# Connectors.net
KiCad netlist of a schematic drawn in Altium Designer
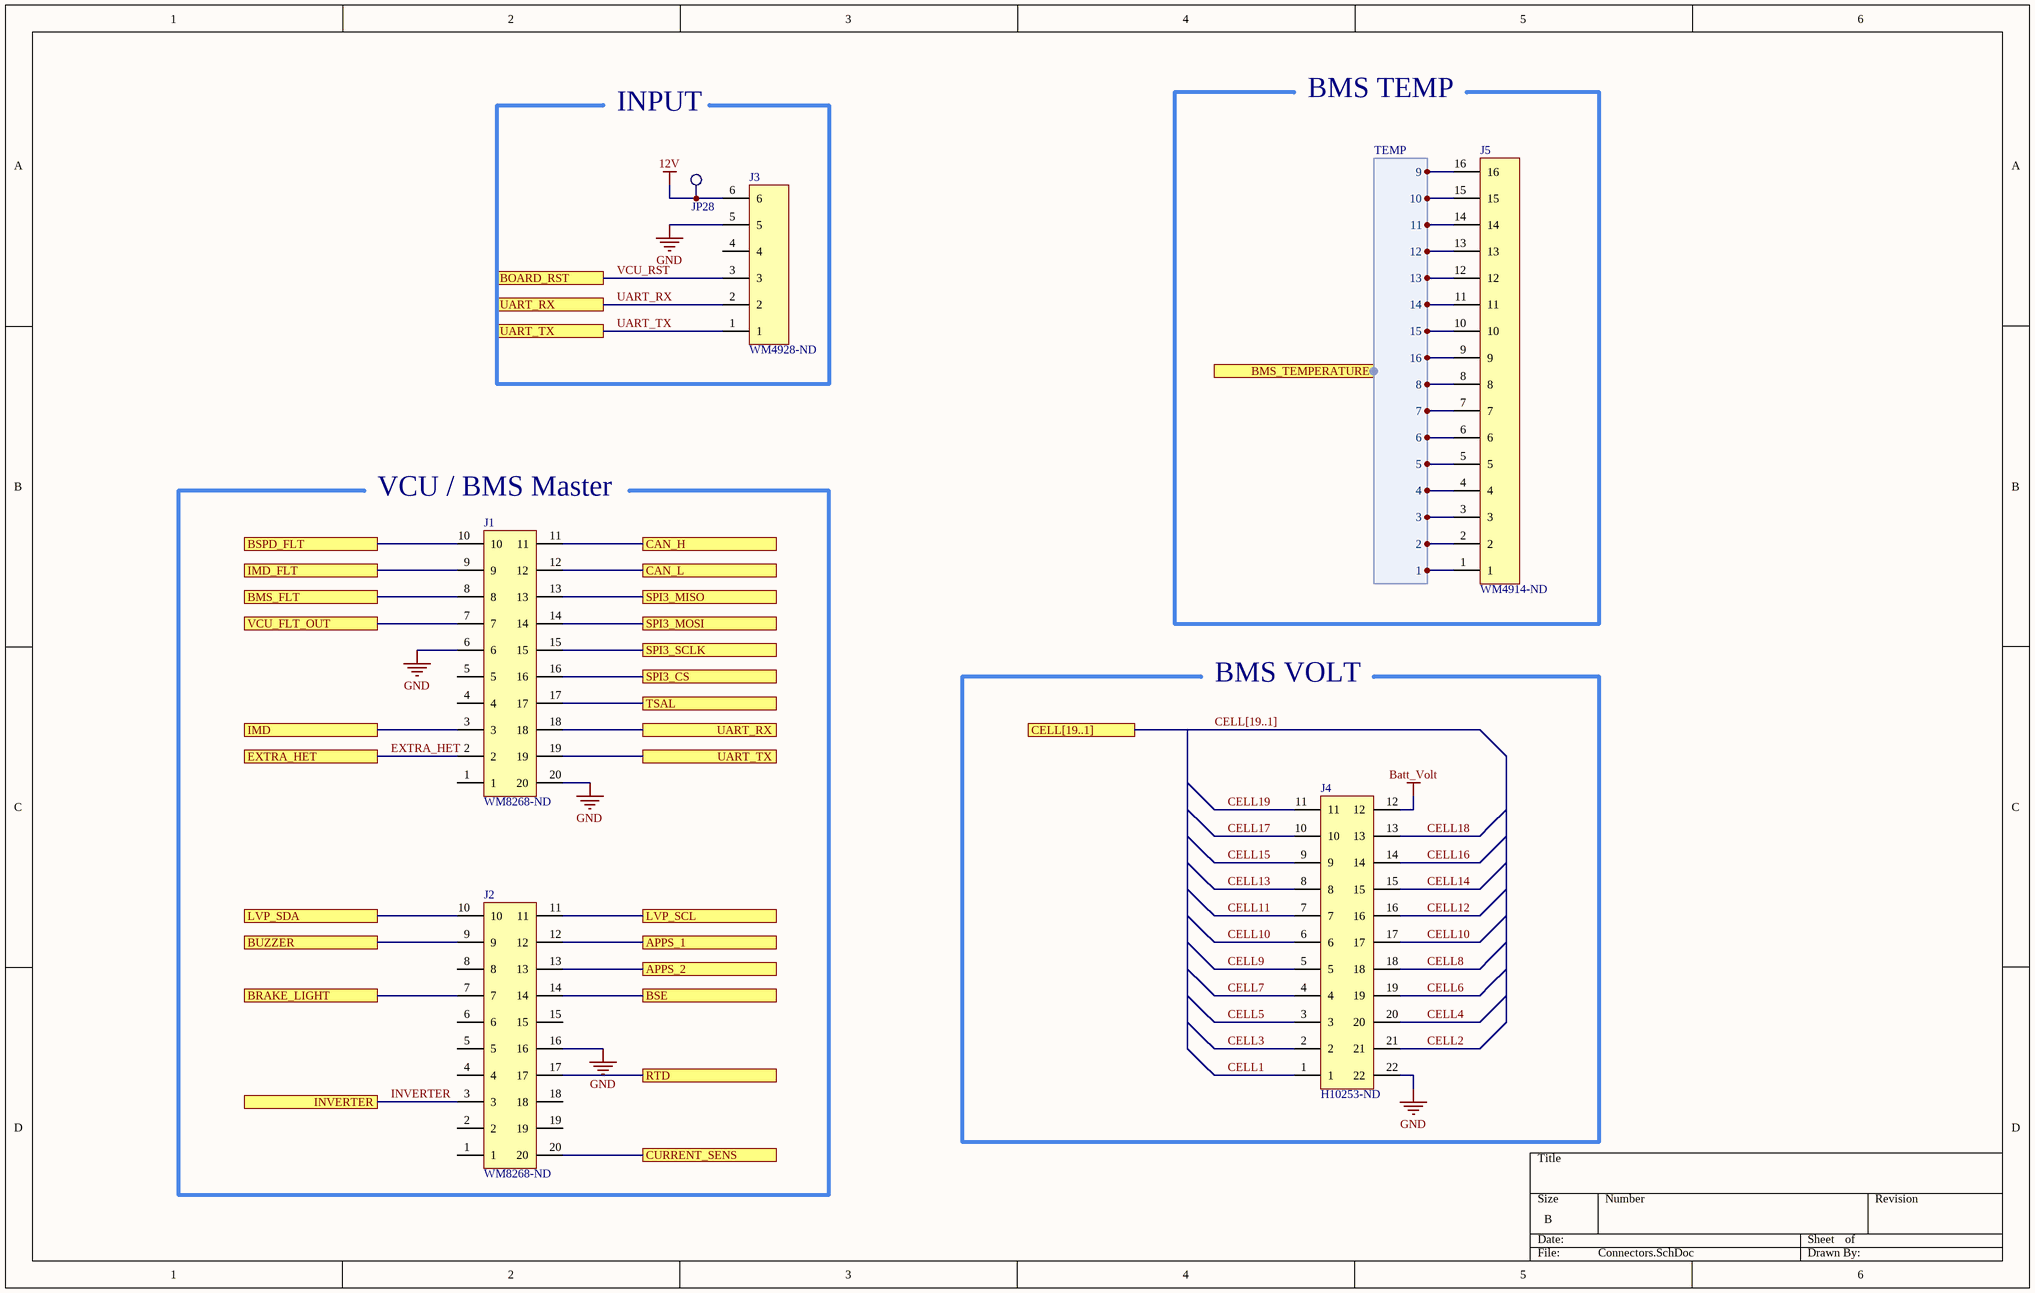
[diagram p0: Connectors.SchDoc]

(export (version "E")
  (design (tool "Eeschema 10.0.6"))
  (components
    (comp (ref "J1")
      (value "WM8268-ND")
      (footprint "2X10PIN")
      (description "CONN HEADER R/A 20POS 2.54MM")
      (fields (field (name "MANUFACTURER") "Molex") (field (name "MANUFACTURER PART NUMBER") "0901303120"))
      (libsource (lib "Connectors") (part "2X10PIN"))
    )
    (comp (ref "J2")
      (value "WM8268-ND")
      (footprint "2X10PIN")
      (description "CONN HEADER R/A 20POS 2.54MM")
      (fields (field (name "MANUFACTURER") "Molex") (field (name "MANUFACTURER PART NUMBER") "0901303120"))
      (libsource (lib "Connectors") (part "2X10PIN"))
    )
    (comp (ref "J3")
      (value "WM4928-ND")
      (footprint "6PIN")
      (description "CONN HEADER R/A 6POS 2.54MM")
      (fields (field (name "MANUFACTURER") "Molex") (field (name "MANUFACTURER PART NUMBER") "70553-0040"))
      (libsource (lib "Connectors") (part "6PIN"))
    )
    (comp (ref "J4")
      (value "H10253-ND")
      (footprint "2X11PIN")
      (description "CONN HEADER R/A 22POS 2MM")
      (fields
        (field (name "MANUFACTURER") "Hirose")
        (field (name "MANUFACTURER PART NUMBER") "DF11-22DP-2DS(24)")
      )
      (libsource (lib "Connectors") (part "2X11PIN"))
    )
    (comp (ref "J5")
      (value "WM4914-ND")
      (footprint "16PIN")
      (description "CONN HEADER R/A 16POS 2.54MM")
      (fields (field (name "MANUFACTURER") "Molex") (field (name "MANUFACTURER PART NUMBER") "0705530015"))
      (libsource (lib "Connectors") (part "16PIN"))
    )
    (comp (ref "JP28")
      (value "Testpoint2")
      (footprint "TP2")
      (description "Single layer pad TP")
      (libsource (lib "Misc") (part "Testpoint2"))
    )
  )
  (nets
    (net (code "2") (name "/1") (class "Default")
      (node (ref "J5") (pin "1") (pinfunction "1_1") (pintype "passive"))
    )
    (net (code "3") (name "/2") (class "Default")
      (node (ref "J5") (pin "2") (pinfunction "2_2") (pintype "passive"))
    )
    (net (code "4") (name "/3") (class "Default")
      (node (ref "J5") (pin "3") (pinfunction "3_3") (pintype "passive"))
    )
    (net (code "5") (name "/4") (class "Default")
      (node (ref "J5") (pin "4") (pinfunction "4_4") (pintype "passive"))
    )
    (net (code "6") (name "/5") (class "Default")
      (node (ref "J5") (pin "5") (pinfunction "5_5") (pintype "passive"))
    )
    (net (code "7") (name "/6") (class "Default")
      (node (ref "J5") (pin "6") (pinfunction "6_6") (pintype "passive"))
    )
    (net (code "8") (name "/7") (class "Default")
      (node (ref "J5") (pin "7") (pinfunction "7_7") (pintype "passive"))
    )
    (net (code "9") (name "/8") (class "Default")
      (node (ref "J5") (pin "8") (pinfunction "8_8") (pintype "passive"))
    )
    (net (code "10") (name "/9") (class "Default")
      (node (ref "J5") (pin "16") (pinfunction "16_16") (pintype "passive"))
    )
    (net (code "11") (name "/10") (class "Default")
      (node (ref "J5") (pin "15") (pinfunction "15_15") (pintype "passive"))
    )
    (net (code "12") (name "/11") (class "Default")
      (node (ref "J5") (pin "14") (pinfunction "14_14") (pintype "passive"))
    )
    (net (code "13") (name "/12") (class "Default")
      (node (ref "J5") (pin "13") (pinfunction "13_13") (pintype "passive"))
    )
    (net (code "14") (name "/13") (class "Default")
      (node (ref "J5") (pin "12") (pinfunction "12_12") (pintype "passive"))
    )
    (net (code "15") (name "/14") (class "Default")
      (node (ref "J5") (pin "11") (pinfunction "11_11") (pintype "passive"))
    )
    (net (code "16") (name "/15") (class "Default")
      (node (ref "J5") (pin "10") (pinfunction "10_10") (pintype "passive"))
    )
    (net (code "17") (name "/16") (class "Default")
      (node (ref "J5") (pin "9") (pinfunction "9_9") (pintype "passive"))
    )
    (net (code "18") (name "/APPS_1") (class "Default")
      (node (ref "J2") (pin "12") (pinfunction "12_12") (pintype "passive"))
    )
    (net (code "19") (name "/APPS_2") (class "Default")
      (node (ref "J2") (pin "13") (pinfunction "13_13") (pintype "passive"))
    )
    (net (code "20") (name "/BMS_FLT") (class "Default")
      (node (ref "J1") (pin "8") (pinfunction "8_8") (pintype "passive"))
    )
    (net (code "21") (name "/BRAKE_LIGHT") (class "Default")
      (node (ref "J2") (pin "7") (pinfunction "7_7") (pintype "passive"))
    )
    (net (code "22") (name "/BSE") (class "Default")
      (node (ref "J2") (pin "14") (pinfunction "14_14") (pintype "passive"))
    )
    (net (code "23") (name "/BSPD_FLT") (class "Default")
      (node (ref "J1") (pin "10") (pinfunction "10_10") (pintype "passive"))
    )
    (net (code "24") (name "/BUZZER") (class "Default")
      (node (ref "J2") (pin "9") (pinfunction "9_9") (pintype "passive"))
    )
    (net (code "25") (name "/CAN_H") (class "Default")
      (node (ref "J1") (pin "11") (pinfunction "11_11") (pintype "passive"))
    )
    (net (code "26") (name "/CAN_L") (class "Default")
      (node (ref "J1") (pin "12") (pinfunction "12_12") (pintype "passive"))
    )
    (net (code "27") (name "/CELL1") (class "Default")
      (node (ref "J4") (pin "1") (pinfunction "1_1") (pintype "passive"))
    )
    (net (code "28") (name "/CELL2") (class "Default")
      (node (ref "J4") (pin "21") (pinfunction "21_21") (pintype "passive"))
    )
    (net (code "29") (name "/CELL3") (class "Default")
      (node (ref "J4") (pin "2") (pinfunction "2_2") (pintype "passive"))
    )
    (net (code "30") (name "/CELL4") (class "Default")
      (node (ref "J4") (pin "20") (pinfunction "20_20") (pintype "passive"))
    )
    (net (code "31") (name "/CELL5") (class "Default")
      (node (ref "J4") (pin "3") (pinfunction "3_3") (pintype "passive"))
    )
    (net (code "32") (name "/CELL6") (class "Default")
      (node (ref "J4") (pin "19") (pinfunction "19_19") (pintype "passive"))
    )
    (net (code "33") (name "/CELL7") (class "Default")
      (node (ref "J4") (pin "4") (pinfunction "4_4") (pintype "passive"))
    )
    (net (code "34") (name "/CELL8") (class "Default")
      (node (ref "J4") (pin "18") (pinfunction "18_18") (pintype "passive"))
    )
    (net (code "35") (name "/CELL9") (class "Default")
      (node (ref "J4") (pin "5") (pinfunction "5_5") (pintype "passive"))
    )
    (net (code "36") (name "/CELL10") (class "Default")
      (node (ref "J4") (pin "17") (pinfunction "17_17") (pintype "passive"))
      (node (ref "J4") (pin "6") (pinfunction "6_6") (pintype "passive"))
    )
    (net (code "37") (name "/CELL11") (class "Default")
      (node (ref "J4") (pin "7") (pinfunction "7_7") (pintype "passive"))
    )
    (net (code "38") (name "/CELL12") (class "Default")
      (node (ref "J4") (pin "16") (pinfunction "16_16") (pintype "passive"))
    )
    (net (code "39") (name "/CELL13") (class "Default")
      (node (ref "J4") (pin "8") (pinfunction "8_8") (pintype "passive"))
    )
    (net (code "40") (name "/CELL14") (class "Default")
      (node (ref "J4") (pin "15") (pinfunction "15_15") (pintype "passive"))
    )
    (net (code "41") (name "/CELL15") (class "Default")
      (node (ref "J4") (pin "9") (pinfunction "9_9") (pintype "passive"))
    )
    (net (code "42") (name "/CELL16") (class "Default")
      (node (ref "J4") (pin "14") (pinfunction "14_14") (pintype "passive"))
    )
    (net (code "43") (name "/CELL17") (class "Default")
      (node (ref "J4") (pin "10") (pinfunction "10_10") (pintype "passive"))
    )
    (net (code "44") (name "/CELL18") (class "Default")
      (node (ref "J4") (pin "13") (pinfunction "13_13") (pintype "passive"))
    )
    (net (code "45") (name "/CELL19") (class "Default")
      (node (ref "J4") (pin "11") (pinfunction "11_11") (pintype "passive"))
    )
    (net (code "47") (name "/CURRENT_SENS") (class "Default")
      (node (ref "J2") (pin "20") (pinfunction "20_20") (pintype "passive"))
    )
    (net (code "48") (name "/EXTRA_HET") (class "Default")
      (node (ref "J1") (pin "2") (pinfunction "2_2") (pintype "passive"))
    )
    (net (code "49") (name "/IMD") (class "Default")
      (node (ref "J1") (pin "3") (pinfunction "3_3") (pintype "passive"))
    )
    (net (code "50") (name "/IMD_FLT") (class "Default")
      (node (ref "J1") (pin "9") (pinfunction "9_9") (pintype "passive"))
    )
    (net (code "51") (name "/INVERTER") (class "Default")
      (node (ref "J2") (pin "3") (pinfunction "3_3") (pintype "passive"))
    )
    (net (code "52") (name "/LVP_SCL") (class "Default")
      (node (ref "J2") (pin "11") (pinfunction "11_11") (pintype "passive"))
    )
    (net (code "53") (name "/LVP_SDA") (class "Default")
      (node (ref "J2") (pin "10") (pinfunction "10_10") (pintype "passive"))
    )
    (net (code "54") (name "/RTD") (class "Default")
      (node (ref "J2") (pin "17") (pinfunction "17_17") (pintype "passive"))
    )
    (net (code "55") (name "/SPI3_CS") (class "Default")
      (node (ref "J1") (pin "16") (pinfunction "16_16") (pintype "passive"))
    )
    (net (code "56") (name "/SPI3_MISO") (class "Default")
      (node (ref "J1") (pin "13") (pinfunction "13_13") (pintype "passive"))
    )
    (net (code "57") (name "/SPI3_MOSI") (class "Default")
      (node (ref "J1") (pin "14") (pinfunction "14_14") (pintype "passive"))
    )
    (net (code "58") (name "/SPI3_SCLK") (class "Default")
      (node (ref "J1") (pin "15") (pinfunction "15_15") (pintype "passive"))
    )
    (net (code "59") (name "/TSAL") (class "Default")
      (node (ref "J1") (pin "17") (pinfunction "17_17") (pintype "passive"))
    )
    (net (code "60") (name "/UART_RX") (class "Default")
      (node (ref "J1") (pin "18") (pinfunction "18_18") (pintype "passive"))
      (node (ref "J3") (pin "2") (pinfunction "2_2") (pintype "passive"))
    )
    (net (code "61") (name "/UART_TX") (class "Default")
      (node (ref "J1") (pin "19") (pinfunction "19_19") (pintype "passive"))
      (node (ref "J3") (pin "1") (pinfunction "1_1") (pintype "passive"))
    )
    (net (code "62") (name "/VCU_FLT_OUT") (class "Default")
      (node (ref "J1") (pin "7") (pinfunction "7_7") (pintype "passive"))
    )
    (net (code "63") (name "/VCU_RST") (class "Default")
      (node (ref "J3") (pin "3") (pinfunction "3_3") (pintype "passive"))
    )
    (net (code "65") (name "12V") (class "Default")
      (node (ref "J3") (pin "6") (pinfunction "6_6") (pintype "passive"))
      (node (ref "JP28") (pin "1") (pinfunction "1_1") (pintype "passive"))
    )
    (net (code "66") (name "Batt_Volt") (class "Default")
      (node (ref "J4") (pin "12") (pinfunction "12_12") (pintype "passive"))
    )
    (net (code "67") (name "GND") (class "Default")
      (node (ref "J1") (pin "20") (pinfunction "20_20") (pintype "passive"))
      (node (ref "J1") (pin "6") (pinfunction "6_6") (pintype "passive"))
      (node (ref "J2") (pin "16") (pinfunction "16_16") (pintype "passive"))
      (node (ref "J3") (pin "5") (pinfunction "5_5") (pintype "passive"))
      (node (ref "J4") (pin "22") (pinfunction "22_22") (pintype "passive"))
    )
    (net (code "68") (name "unconnected-(J1-Pad1)") (class "Default")
      (node (ref "J1") (pin "1") (pinfunction "1_1") (pintype "passive"))
    )
    (net (code "69") (name "unconnected-(J1-Pad4)") (class "Default")
      (node (ref "J1") (pin "4") (pinfunction "4_4") (pintype "passive"))
    )
    (net (code "70") (name "unconnected-(J1-Pad5)") (class "Default")
      (node (ref "J1") (pin "5") (pinfunction "5_5") (pintype "passive"))
    )
    (net (code "71") (name "unconnected-(J2-Pad1)") (class "Default")
      (node (ref "J2") (pin "1") (pinfunction "1_1") (pintype "passive"))
    )
    (net (code "72") (name "unconnected-(J2-Pad2)") (class "Default")
      (node (ref "J2") (pin "2") (pinfunction "2_2") (pintype "passive"))
    )
    (net (code "73") (name "unconnected-(J2-Pad4)") (class "Default")
      (node (ref "J2") (pin "4") (pinfunction "4_4") (pintype "passive"))
    )
    (net (code "74") (name "unconnected-(J2-Pad5)") (class "Default")
      (node (ref "J2") (pin "5") (pinfunction "5_5") (pintype "passive"))
    )
    (net (code "75") (name "unconnected-(J2-Pad6)") (class "Default")
      (node (ref "J2") (pin "6") (pinfunction "6_6") (pintype "passive"))
    )
    (net (code "76") (name "unconnected-(J2-Pad8)") (class "Default")
      (node (ref "J2") (pin "8") (pinfunction "8_8") (pintype "passive"))
    )
    (net (code "77") (name "unconnected-(J2-Pad15)") (class "Default")
      (node (ref "J2") (pin "15") (pinfunction "15_15") (pintype "passive"))
    )
    (net (code "78") (name "unconnected-(J2-Pad18)") (class "Default")
      (node (ref "J2") (pin "18") (pinfunction "18_18") (pintype "passive"))
    )
    (net (code "79") (name "unconnected-(J2-Pad19)") (class "Default")
      (node (ref "J2") (pin "19") (pinfunction "19_19") (pintype "passive"))
    )
    (net (code "80") (name "unconnected-(J3-Pad4)") (class "Default")
      (node (ref "J3") (pin "4") (pinfunction "4_4") (pintype "passive"))
    )
  )
)
